# StmPulse-V1-InProgress.net
KiCad netlist of a schematic drawn in EAGLE
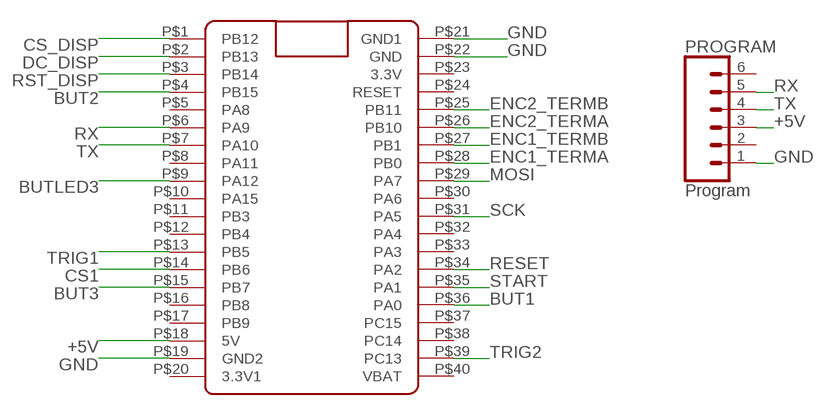
[diagram p0: schematic, sheet 1]
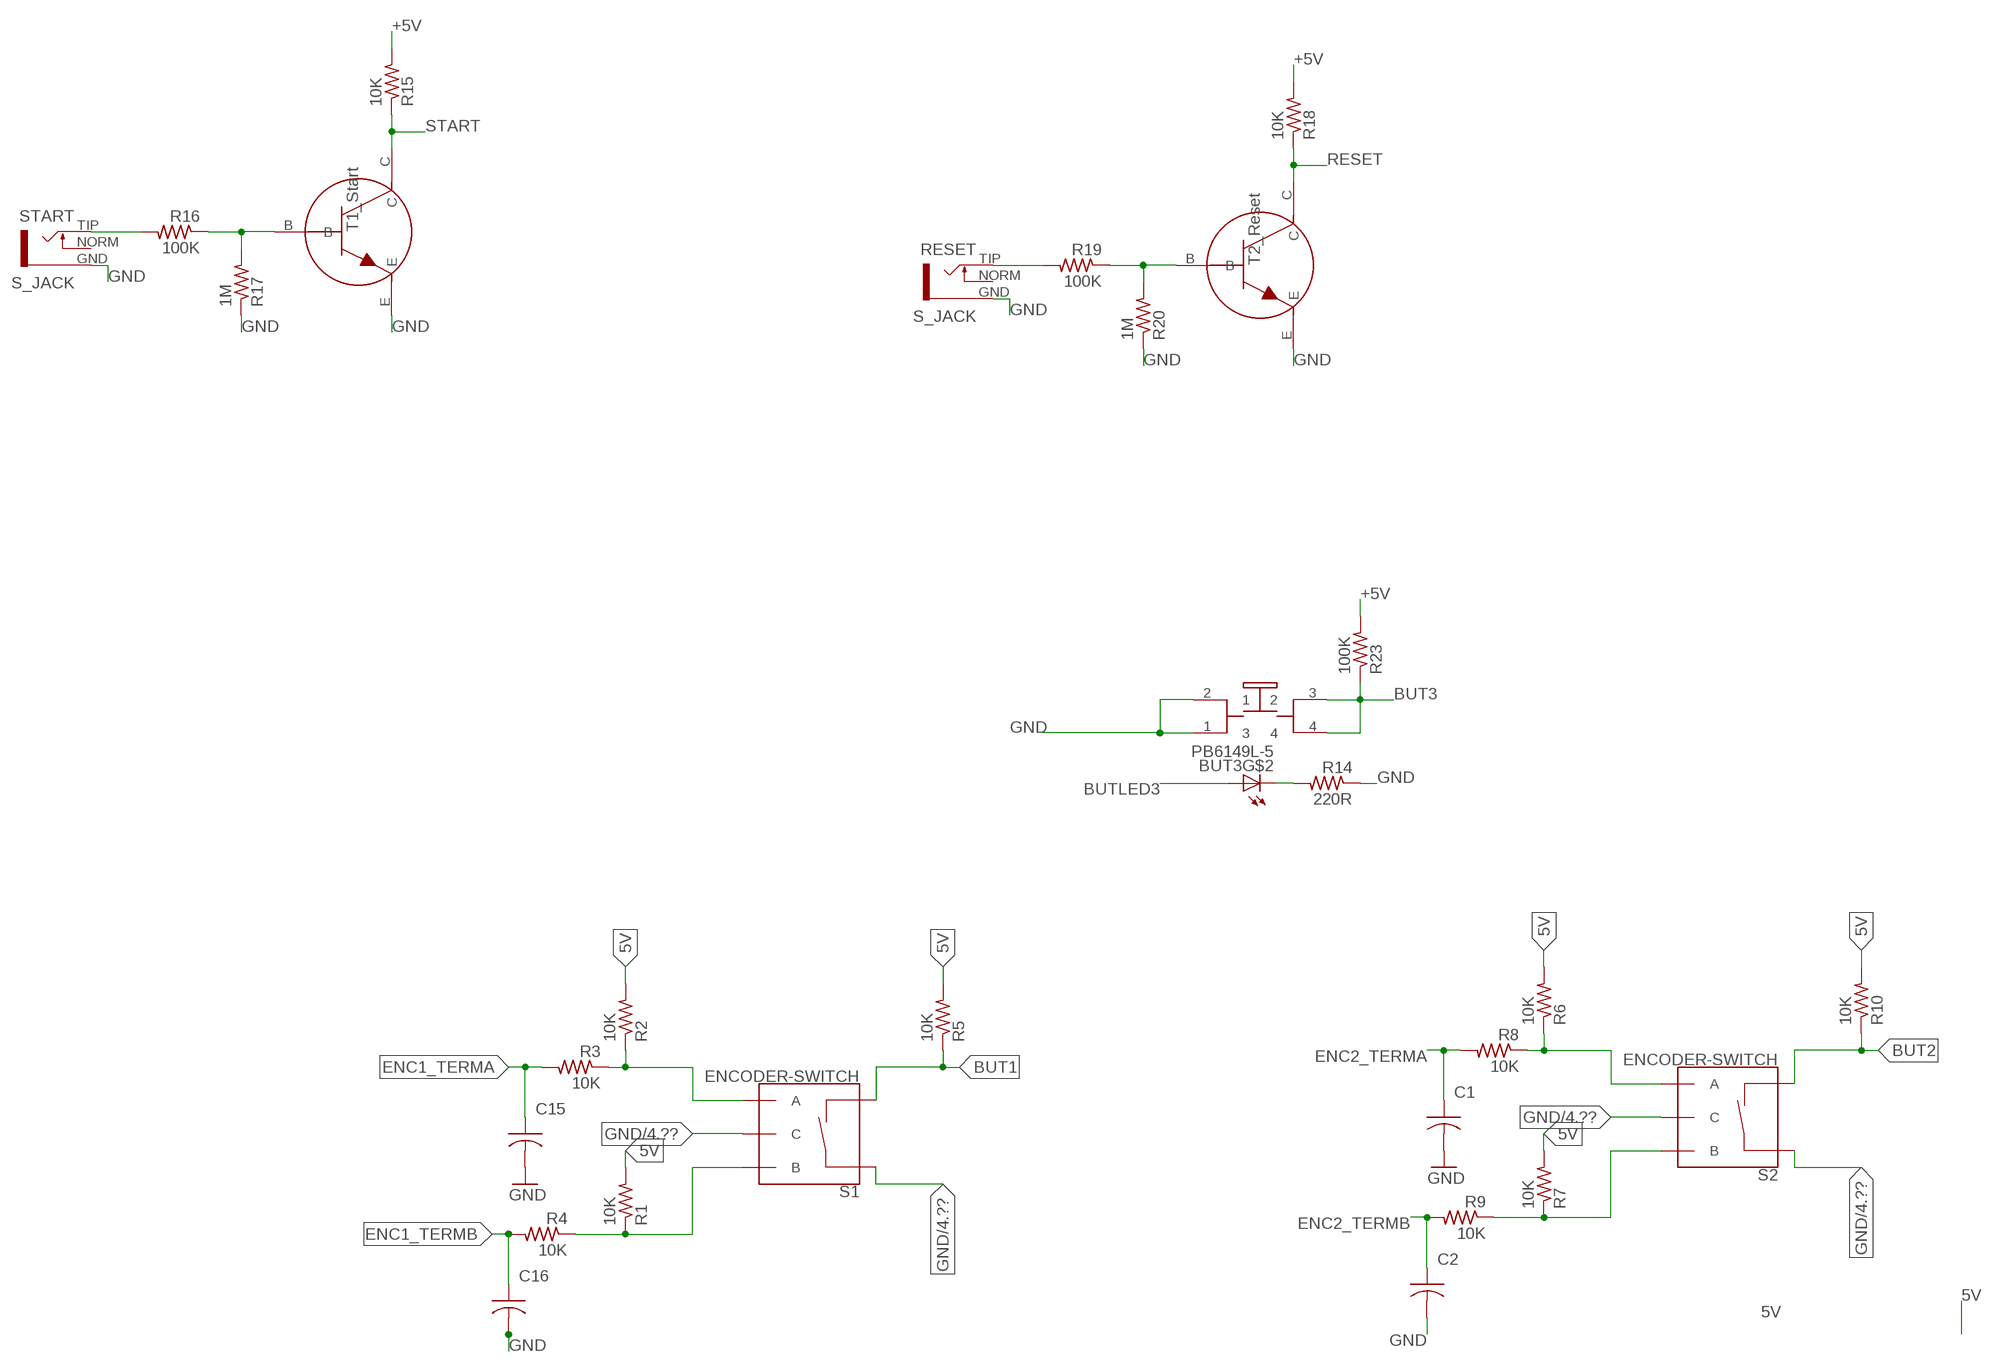
[diagram p1: schematic, sheet 2]
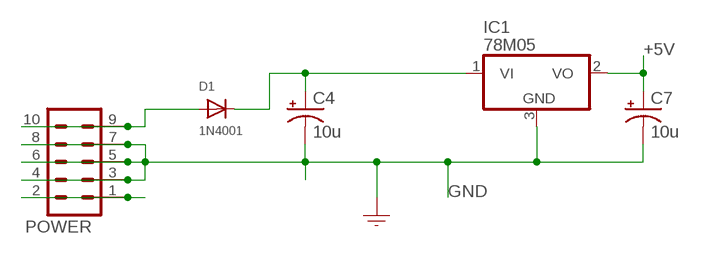
[diagram p2: schematic, sheet 3]
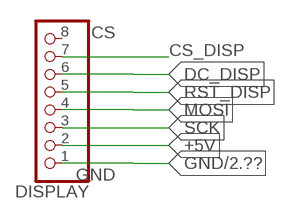
[diagram p3: schematic, sheet 4]
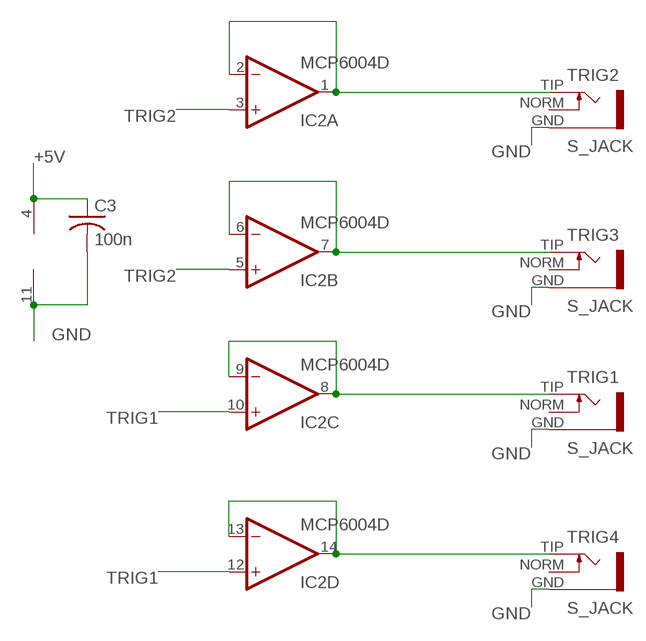
[diagram p4: schematic, sheet 5]
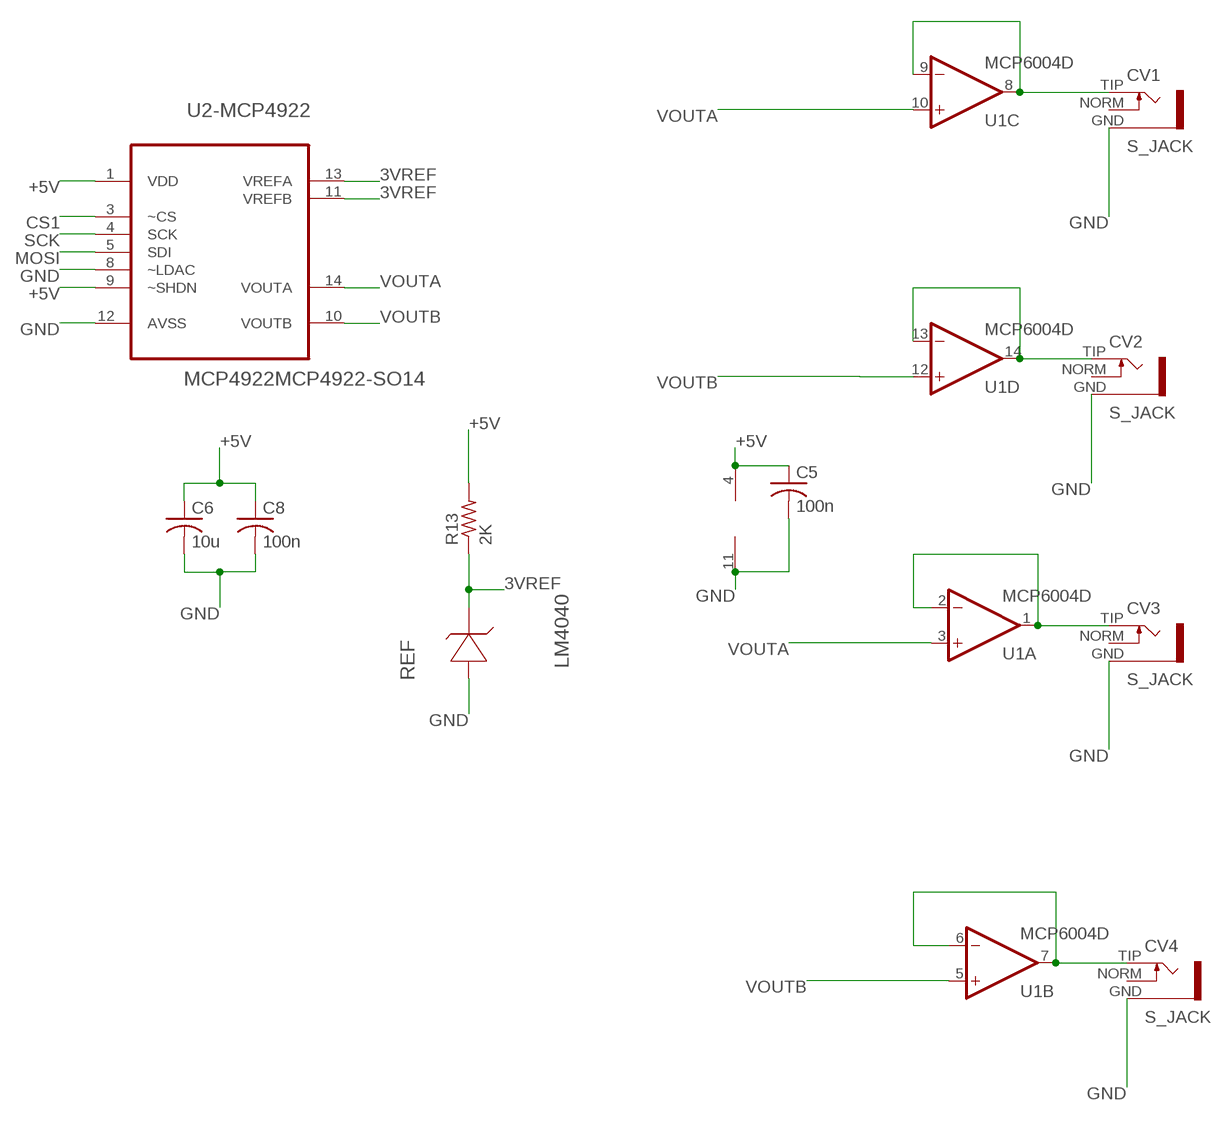
[diagram p5: schematic, sheet 6]

(export (version "E")
  (design (tool "Eeschema 10.0.6"))
  (components
    (comp (ref "PROGRAM")
      (value "Program")
      (footprint "eagle-import:1X06")
      (libsource (lib "eagle-import") (part "CONN_06SILK_FEMALE_PTH"))
    )
    (comp (ref "U$1")
      (value "Blue Pill")
      (footprint "eagle-import:BLUE_PILL")
      (libsource (lib "eagle-import") (part "BLUE_PILL"))
    )
    (comp (ref "DISPLAY")
      (value "MICROBUILDER_HEADER-1X8ROUND")
      (footprint "eagle-import:MICROBUILDER_1X08_ROUND")
      (libsource (lib "eagle-import") (part "MICROBUILDER_HEADER-1X8ROUND"))
    )
    (comp (ref "C3")
      (value "100n")
      (footprint "eagle-import:C0805K")
      (libsource (lib "eagle-import") (part "C-USC0805K"))
    )
    (comp (ref "IC2")
      (value "MCP6004D")
      (footprint "eagle-import:SO14")
      (libsource (lib "eagle-import") (part "MCP6004D"))
    )
    (comp (ref "TRIG1")
      (value "S_JACK")
      (footprint "eagle-import:S_JACK")
      (libsource (lib "eagle-import") (part "S_JACK"))
    )
    (comp (ref "TRIG2")
      (value "S_JACK")
      (footprint "eagle-import:S_JACK")
      (libsource (lib "eagle-import") (part "S_JACK"))
    )
    (comp (ref "TRIG3")
      (value "S_JACK")
      (footprint "eagle-import:S_JACK")
      (libsource (lib "eagle-import") (part "S_JACK"))
    )
    (comp (ref "TRIG4")
      (value "S_JACK")
      (footprint "eagle-import:S_JACK")
      (libsource (lib "eagle-import") (part "S_JACK"))
    )
    (comp (ref "C5")
      (value "100n")
      (footprint "eagle-import:C0805K")
      (libsource (lib "eagle-import") (part "C-USC0805K"))
    )
    (comp (ref "C6")
      (value "10u")
      (footprint "eagle-import:C0805K")
      (libsource (lib "eagle-import") (part "C-USC0805K"))
    )
    (comp (ref "C8")
      (value "100n")
      (footprint "eagle-import:C0805K")
      (libsource (lib "eagle-import") (part "C-USC0805K"))
    )
    (comp (ref "CV1")
      (value "S_JACK")
      (footprint "eagle-import:S_JACK")
      (libsource (lib "eagle-import") (part "S_JACK"))
    )
    (comp (ref "CV2")
      (value "S_JACK")
      (footprint "eagle-import:S_JACK")
      (libsource (lib "eagle-import") (part "S_JACK"))
    )
    (comp (ref "CV3")
      (value "S_JACK")
      (footprint "eagle-import:S_JACK")
      (libsource (lib "eagle-import") (part "S_JACK"))
    )
    (comp (ref "CV4")
      (value "S_JACK")
      (footprint "eagle-import:S_JACK")
      (libsource (lib "eagle-import") (part "S_JACK"))
    )
    (comp (ref "R13")
      (value "2K")
      (footprint "eagle-import:R0805")
      (libsource (lib "eagle-import") (part "R-US_R0805"))
    )
    (comp (ref "REF")
      (value "LM4040")
      (footprint "eagle-import:SOT95P237X112-3N")
      (fields
        (field (name "MPN") "LM4040A50IDBZT")
        (field (name "MPN_1") "LM4040A30IDBZT")
        (field (name "RS-PART") "809-6343")
      )
      (libsource (lib "eagle-import") (part "LM4040A30IDBZT"))
    )
    (comp (ref "U1")
      (value "MCP6004D")
      (footprint "eagle-import:SO14")
      (fields (field (name "RS-PART") "628-3481 (10)"))
      (libsource (lib "eagle-import") (part "MCP6004D"))
    )
    (comp (ref "U2-MCP4922")
      (value "MCP4922MCP4922-SO14")
      (footprint "eagle-import:SO14")
      (fields (field (name "RS-PART") "402-910 "))
      (libsource (lib "eagle-import") (part "MCP4922MCP4922-SO14"))
    )
    (comp (ref "C4")
      (value "10u")
      (footprint "eagle-import:153CLV-0505")
      (libsource (lib "eagle-import") (part "CAPACITOR_POL-US153CLV-0505"))
    )
    (comp (ref "C7")
      (value "10u")
      (footprint "eagle-import:153CLV-0505")
      (libsource (lib "eagle-import") (part "CAPACITOR_POL-US153CLV-0505"))
    )
    (comp (ref "D1")
      (value "1N4001")
      (footprint "eagle-import:SMADIODE")
      (libsource (lib "eagle-import") (part "DIODESMA"))
    )
    (comp (ref "IC1")
      (value "78M05")
      (footprint "eagle-import:TO252")
      (libsource (lib "eagle-import") (part "VOLTAGE_REG_POSDT05"))
    )
    (comp (ref "POWER")
      (value "CONN_05X2SHD_SMD")
      (footprint "eagle-import:2X5-SHROUDED_SMD")
      (libsource (lib "eagle-import") (part "CONN_05X2SHD_SMD"))
    )
    (comp (ref "BUT3")
      (value "PB6149L-5")
      (footprint "eagle-import:PB6149L")
      (libsource (lib "eagle-import") (part "PB6149L-5"))
    )
    (comp (ref "C1")
      (value "10nF")
      (footprint "eagle-import:C0805")
      (libsource (lib "eagle-import") (part "C-USC0805"))
    )
    (comp (ref "C2")
      (value "10nF")
      (footprint "eagle-import:C0805")
      (libsource (lib "eagle-import") (part "C-USC0805"))
    )
    (comp (ref "C15")
      (value "10nF")
      (footprint "eagle-import:C0805")
      (libsource (lib "eagle-import") (part "C-USC0805"))
    )
    (comp (ref "C16")
      (value "10nF")
      (footprint "eagle-import:C0805")
      (libsource (lib "eagle-import") (part "C-USC0805"))
    )
    (comp (ref "R1")
      (value "10K")
      (footprint "eagle-import:R0805")
      (libsource (lib "eagle-import") (part "R-US_R0805"))
    )
    (comp (ref "R2")
      (value "10K")
      (footprint "eagle-import:R0805")
      (libsource (lib "eagle-import") (part "R-US_R0805"))
    )
    (comp (ref "R3")
      (value "10K")
      (footprint "eagle-import:R0805")
      (libsource (lib "eagle-import") (part "R-US_R0805"))
    )
    (comp (ref "R4")
      (value "10K")
      (footprint "eagle-import:R0805")
      (libsource (lib "eagle-import") (part "R-US_R0805"))
    )
    (comp (ref "R5")
      (value "10K")
      (footprint "eagle-import:R0805")
      (libsource (lib "eagle-import") (part "R-US_R0805"))
    )
    (comp (ref "R6")
      (value "10K")
      (footprint "eagle-import:R0805")
      (libsource (lib "eagle-import") (part "R-US_R0805"))
    )
    (comp (ref "R7")
      (value "10K")
      (footprint "eagle-import:R0805")
      (libsource (lib "eagle-import") (part "R-US_R0805"))
    )
    (comp (ref "R8")
      (value "10K")
      (footprint "eagle-import:R0805")
      (libsource (lib "eagle-import") (part "R-US_R0805"))
    )
    (comp (ref "R9")
      (value "10K")
      (footprint "eagle-import:R0805")
      (libsource (lib "eagle-import") (part "R-US_R0805"))
    )
    (comp (ref "R10")
      (value "10K")
      (footprint "eagle-import:R0805")
      (libsource (lib "eagle-import") (part "R-US_R0805"))
    )
    (comp (ref "R14")
      (value "220R")
      (footprint "eagle-import:R0805")
      (libsource (lib "eagle-import") (part "R-US_R0805"))
    )
    (comp (ref "R15")
      (value "10K")
      (footprint "eagle-import:R0805")
      (libsource (lib "eagle-import") (part "R-US_R0805"))
    )
    (comp (ref "R16")
      (value "100K")
      (footprint "eagle-import:R0805")
      (libsource (lib "eagle-import") (part "R-US_R0805"))
    )
    (comp (ref "R17")
      (value "1M")
      (footprint "eagle-import:R0805")
      (libsource (lib "eagle-import") (part "R-US_R0805"))
    )
    (comp (ref "R18")
      (value "10K")
      (footprint "eagle-import:R0805")
      (libsource (lib "eagle-import") (part "R-US_R0805"))
    )
    (comp (ref "R19")
      (value "100K")
      (footprint "eagle-import:R0805")
      (libsource (lib "eagle-import") (part "R-US_R0805"))
    )
    (comp (ref "R20")
      (value "1M")
      (footprint "eagle-import:R0805")
      (libsource (lib "eagle-import") (part "R-US_R0805"))
    )
    (comp (ref "R23")
      (value "100K")
      (footprint "eagle-import:R0805")
      (libsource (lib "eagle-import") (part "R-US_R0805"))
    )
    (comp (ref "RESET")
      (value "S_JACK")
      (footprint "eagle-import:S_JACK")
      (libsource (lib "eagle-import") (part "S_JACK"))
    )
    (comp (ref "S1")
      (value "ENCODER-SWITCH")
      (footprint "eagle-import:ROTARY_ENC_PLAIN")
      (libsource (lib "eagle-import") (part "ENCODER-SWITCH"))
    )
    (comp (ref "S2")
      (value "ENCODER-SWITCH")
      (footprint "eagle-import:ROTARY_ENC_PLAIN")
      (libsource (lib "eagle-import") (part "ENCODER-SWITCH"))
    )
    (comp (ref "START")
      (value "S_JACK")
      (footprint "eagle-import:S_JACK")
      (libsource (lib "eagle-import") (part "S_JACK"))
    )
    (comp (ref "T1_CLOCK")
      (value "2N3904")
      (footprint "eagle-import:TRANSISTOR_SINGLE_N-TYPE")
      (fields (field (name "LABLEL") "T1_Start") (field (name "RS-PART") "725-8616 "))
      (libsource (lib "eagle-import") (part "TRANSISTOR_MMBT3904"))
    )
    (comp (ref "T2_RESET")
      (value "TRANSISTOR_MMBT3904")
      (footprint "eagle-import:TRANSISTOR_SINGLE_N-TYPE")
      (fields (field (name "LABEL") "T2_Reset") (field (name "RS-PART") "725-8616 "))
      (libsource (lib "eagle-import") (part "TRANSISTOR_MMBT3904"))
    )
  )
  (nets
    (net (code "1") (name "+5V") (class "Default")
      (node (ref "C3") (pin "1") (pinfunction "1_1") (pintype "passive"))
      (node (ref "C5") (pin "1") (pinfunction "1_1") (pintype "passive"))
      (node (ref "C6") (pin "1") (pinfunction "1_1") (pintype "passive"))
      (node (ref "C7") (pin "+") (pinfunction "+_+") (pintype "passive"))
      (node (ref "C8") (pin "1") (pinfunction "1_1") (pintype "passive"))
      (node (ref "DISPLAY") (pin "2") (pinfunction "2_2") (pintype "passive"))
      (node (ref "IC1") (pin "2") (pinfunction "VO_2") (pintype "passive"))
      (node (ref "IC2") (pin "4") (pinfunction "V+_4") (pintype "power_in"))
      (node (ref "PROGRAM") (pin "3") (pinfunction "3_3") (pintype "passive"))
      (node (ref "R13") (pin "2") (pinfunction "2_2") (pintype "passive"))
      (node (ref "R15") (pin "2") (pinfunction "2_2") (pintype "passive"))
      (node (ref "R18") (pin "2") (pinfunction "2_2") (pintype "passive"))
      (node (ref "R23") (pin "2") (pinfunction "2_2") (pintype "passive"))
      (node (ref "U$1") (pin "P$18") (pinfunction "5V_P$18") (pintype "bidirectional"))
      (node (ref "U1") (pin "4") (pinfunction "V+_4") (pintype "power_in"))
      (node (ref "U2-MCP4922") (pin "1") (pinfunction "VDD_1") (pintype "power_in"))
      (node (ref "U2-MCP4922") (pin "9") (pinfunction "~{SHDN}_9") (pintype "bidirectional"))
    )
    (net (code "2") (name "3VREF") (class "Default")
      (node (ref "R13") (pin "1") (pinfunction "1_1") (pintype "passive"))
      (node (ref "REF") (pin "1") (pinfunction "CATHODE_1") (pintype "output"))
      (node (ref "U2-MCP4922") (pin "11") (pinfunction "VREFB_11") (pintype "bidirectional"))
      (node (ref "U2-MCP4922") (pin "13") (pinfunction "VREFA_13") (pintype "input"))
    )
    (net (code "3") (name "5V") (class "Default")
      (node (ref "R1") (pin "2") (pinfunction "2_2") (pintype "passive"))
      (node (ref "R10") (pin "2") (pinfunction "2_2") (pintype "passive"))
      (node (ref "R2") (pin "2") (pinfunction "2_2") (pintype "passive"))
      (node (ref "R5") (pin "2") (pinfunction "2_2") (pintype "passive"))
      (node (ref "R6") (pin "2") (pinfunction "2_2") (pintype "passive"))
      (node (ref "R7") (pin "2") (pinfunction "2_2") (pintype "passive"))
    )
    (net (code "4") (name "BUT1") (class "Default")
      (node (ref "R5") (pin "1") (pinfunction "1_1") (pintype "passive"))
      (node (ref "S1") (pin "SW-") (pinfunction "SW-_SW-") (pintype "bidirectional"))
      (node (ref "U$1") (pin "P$36") (pinfunction "PA0_P$36") (pintype "bidirectional"))
    )
    (net (code "5") (name "BUT2") (class "Default")
      (node (ref "R10") (pin "1") (pinfunction "1_1") (pintype "passive"))
      (node (ref "S2") (pin "SW-") (pinfunction "SW-_SW-") (pintype "bidirectional"))
      (node (ref "U$1") (pin "P$4") (pinfunction "PB15_P$4") (pintype "bidirectional"))
    )
    (net (code "6") (name "BUT3") (class "Default")
      (node (ref "BUT3") (pin "3") (pinfunction "2_3") (pintype "bidirectional"))
      (node (ref "BUT3") (pin "4") (pinfunction "4_4") (pintype "bidirectional"))
      (node (ref "R23") (pin "1") (pinfunction "1_1") (pintype "passive"))
      (node (ref "U$1") (pin "P$15") (pinfunction "PB7_P$15") (pintype "bidirectional"))
    )
    (net (code "7") (name "BUTLED3") (class "Default")
      (node (ref "BUT3") (pin "A") (pinfunction "A_A") (pintype "passive"))
      (node (ref "U$1") (pin "P$9") (pinfunction "PA12_P$9") (pintype "bidirectional"))
    )
    (net (code "8") (name "CS1") (class "Default")
      (node (ref "U$1") (pin "P$14") (pinfunction "PB6_P$14") (pintype "bidirectional"))
      (node (ref "U2-MCP4922") (pin "3") (pinfunction "~{CS}_3") (pintype "input"))
    )
    (net (code "9") (name "CS_DISP") (class "Default")
      (node (ref "DISPLAY") (pin "7") (pinfunction "7_7") (pintype "passive"))
      (node (ref "U$1") (pin "P$1") (pinfunction "PB12_P$1") (pintype "bidirectional"))
    )
    (net (code "10") (name "DC_DISP") (class "Default")
      (node (ref "DISPLAY") (pin "6") (pinfunction "6_6") (pintype "passive"))
      (node (ref "U$1") (pin "P$2") (pinfunction "PB13_P$2") (pintype "bidirectional"))
    )
    (net (code "11") (name "ENC1_TERMA") (class "Default")
      (node (ref "C15") (pin "1") (pinfunction "1_1") (pintype "passive"))
      (node (ref "R3") (pin "2") (pinfunction "2_2") (pintype "passive"))
      (node (ref "U$1") (pin "P$28") (pinfunction "PB0_P$28") (pintype "bidirectional"))
    )
    (net (code "12") (name "ENC1_TERMB") (class "Default")
      (node (ref "C16") (pin "1") (pinfunction "1_1") (pintype "passive"))
      (node (ref "R4") (pin "2") (pinfunction "2_2") (pintype "passive"))
      (node (ref "U$1") (pin "P$27") (pinfunction "PB1_P$27") (pintype "bidirectional"))
    )
    (net (code "13") (name "ENC2_TERMA") (class "Default")
      (node (ref "C1") (pin "1") (pinfunction "1_1") (pintype "passive"))
      (node (ref "R8") (pin "2") (pinfunction "2_2") (pintype "passive"))
      (node (ref "U$1") (pin "P$26") (pinfunction "PB10_P$26") (pintype "bidirectional"))
    )
    (net (code "14") (name "ENC2_TERMB") (class "Default")
      (node (ref "C2") (pin "1") (pinfunction "1_1") (pintype "passive"))
      (node (ref "R9") (pin "2") (pinfunction "2_2") (pintype "passive"))
      (node (ref "U$1") (pin "P$25") (pinfunction "PB11_P$25") (pintype "bidirectional"))
    )
    (net (code "15") (name "GND") (class "Default")
      (node (ref "BUT3") (pin "1") (pinfunction "3_1") (pintype "bidirectional"))
      (node (ref "BUT3") (pin "2") (pinfunction "1_2") (pintype "bidirectional"))
      (node (ref "C1") (pin "2") (pinfunction "2_2") (pintype "passive"))
      (node (ref "C15") (pin "2") (pinfunction "2_2") (pintype "passive"))
      (node (ref "C16") (pin "2") (pinfunction "2_2") (pintype "passive"))
      (node (ref "C2") (pin "2") (pinfunction "2_2") (pintype "passive"))
      (node (ref "C3") (pin "2") (pinfunction "2_2") (pintype "passive"))
      (node (ref "C4") (pin "-") (pinfunction "-_-") (pintype "passive"))
      (node (ref "C5") (pin "2") (pinfunction "2_2") (pintype "passive"))
      (node (ref "C6") (pin "2") (pinfunction "2_2") (pintype "passive"))
      (node (ref "C7") (pin "-") (pinfunction "-_-") (pintype "passive"))
      (node (ref "C8") (pin "2") (pinfunction "2_2") (pintype "passive"))
      (node (ref "CV1") (pin "GND") (pinfunction "GND_GND") (pintype "passive"))
      (node (ref "CV2") (pin "GND") (pinfunction "GND_GND") (pintype "passive"))
      (node (ref "CV3") (pin "GND") (pinfunction "GND_GND") (pintype "passive"))
      (node (ref "CV4") (pin "GND") (pinfunction "GND_GND") (pintype "passive"))
      (node (ref "DISPLAY") (pin "1") (pinfunction "1_1") (pintype "passive"))
      (node (ref "IC1") (pin "3") (pinfunction "GND_3") (pintype "passive"))
      (node (ref "IC2") (pin "11") (pinfunction "V-_11") (pintype "power_in"))
      (node (ref "POWER") (pin "3") (pinfunction "3_3") (pintype "passive"))
      (node (ref "POWER") (pin "4") (pinfunction "4_4") (pintype "passive"))
      (node (ref "POWER") (pin "5") (pinfunction "5_5") (pintype "passive"))
      (node (ref "POWER") (pin "6") (pinfunction "6_6") (pintype "passive"))
      (node (ref "POWER") (pin "7") (pinfunction "7_7") (pintype "passive"))
      (node (ref "POWER") (pin "8") (pinfunction "8_8") (pintype "passive"))
      (node (ref "PROGRAM") (pin "1") (pinfunction "1_1") (pintype "passive"))
      (node (ref "R14") (pin "1") (pinfunction "1_1") (pintype "passive"))
      (node (ref "R17") (pin "1") (pinfunction "1_1") (pintype "passive"))
      (node (ref "R20") (pin "1") (pinfunction "1_1") (pintype "passive"))
      (node (ref "REF") (pin "2") (pinfunction "ANODE_2") (pintype "input"))
      (node (ref "RESET") (pin "GND") (pinfunction "GND_GND") (pintype "passive"))
      (node (ref "S1") (pin "C") (pinfunction "C_C") (pintype "bidirectional"))
      (node (ref "S1") (pin "SW+") (pinfunction "SW+_SW+") (pintype "bidirectional"))
      (node (ref "S2") (pin "C") (pinfunction "C_C") (pintype "bidirectional"))
      (node (ref "S2") (pin "SW+") (pinfunction "SW+_SW+") (pintype "bidirectional"))
      (node (ref "START") (pin "GND") (pinfunction "GND_GND") (pintype "passive"))
      (node (ref "T1_CLOCK") (pin "E") (pinfunction "E_E") (pintype "bidirectional"))
      (node (ref "T2_RESET") (pin "E") (pinfunction "E_E") (pintype "bidirectional"))
      (node (ref "TRIG1") (pin "GND") (pinfunction "GND_GND") (pintype "passive"))
      (node (ref "TRIG2") (pin "GND") (pinfunction "GND_GND") (pintype "passive"))
      (node (ref "TRIG3") (pin "GND") (pinfunction "GND_GND") (pintype "passive"))
      (node (ref "TRIG4") (pin "GND") (pinfunction "GND_GND") (pintype "passive"))
      (node (ref "U$1") (pin "P$19") (pinfunction "GND2_P$19") (pintype "bidirectional"))
      (node (ref "U$1") (pin "P$21") (pinfunction "GND1_P$21") (pintype "power_in"))
      (node (ref "U$1") (pin "P$22") (pinfunction "GND_P$22") (pintype "bidirectional"))
      (node (ref "U1") (pin "11") (pinfunction "V-_11") (pintype "power_in"))
      (node (ref "U2-MCP4922") (pin "12") (pinfunction "AVSS_12") (pintype "passive"))
      (node (ref "U2-MCP4922") (pin "8") (pinfunction "~{LDAC}_8") (pintype "input"))
    )
    (net (code "16") (name "MOSI") (class "Default")
      (node (ref "DISPLAY") (pin "4") (pinfunction "4_4") (pintype "passive"))
      (node (ref "U$1") (pin "P$29") (pinfunction "PA7_P$29") (pintype "bidirectional"))
      (node (ref "U2-MCP4922") (pin "5") (pinfunction "SDI_5") (pintype "input"))
    )
    (net (code "17") (name "Net-(BUT3B-C)") (class "Default")
      (node (ref "BUT3") (pin "K") (pinfunction "C_K") (pintype "passive"))
      (node (ref "R14") (pin "2") (pinfunction "2_2") (pintype "passive"))
    )
    (net (code "18") (name "Net-(D1-PadA)") (class "Default")
      (node (ref "D1") (pin "A") (pinfunction "A_A") (pintype "passive"))
      (node (ref "POWER") (pin "10") (pinfunction "10_10") (pintype "passive"))
      (node (ref "POWER") (pin "9") (pinfunction "9_9") (pintype "passive"))
    )
    (net (code "19") (name "Net-(IC1-VI)") (class "Default")
      (node (ref "C4") (pin "+") (pinfunction "+_+") (pintype "passive"))
      (node (ref "D1") (pin "C") (pinfunction "C_C") (pintype "passive"))
      (node (ref "IC1") (pin "1") (pinfunction "VI_1") (pintype "input"))
    )
    (net (code "20") (name "Net-(IC2A--IN)") (class "Default")
      (node (ref "IC2") (pin "1") (pinfunction "OUT_1") (pintype "output"))
      (node (ref "IC2") (pin "2") (pinfunction "-IN_2") (pintype "input"))
      (node (ref "TRIG2") (pin "TIP") (pinfunction "TIP_TIP") (pintype "passive"))
    )
    (net (code "21") (name "Net-(IC2B--IN)") (class "Default")
      (node (ref "IC2") (pin "6") (pinfunction "-IN_6") (pintype "input"))
      (node (ref "IC2") (pin "7") (pinfunction "OUT_7") (pintype "output"))
      (node (ref "TRIG3") (pin "TIP") (pinfunction "TIP_TIP") (pintype "passive"))
    )
    (net (code "22") (name "Net-(IC2C--IN)") (class "Default")
      (node (ref "IC2") (pin "8") (pinfunction "OUT_8") (pintype "output"))
      (node (ref "IC2") (pin "9") (pinfunction "-IN_9") (pintype "input"))
      (node (ref "TRIG1") (pin "TIP") (pinfunction "TIP_TIP") (pintype "passive"))
    )
    (net (code "23") (name "Net-(IC2D--IN)") (class "Default")
      (node (ref "IC2") (pin "13") (pinfunction "-IN_13") (pintype "input"))
      (node (ref "IC2") (pin "14") (pinfunction "OUT_14") (pintype "output"))
      (node (ref "TRIG4") (pin "TIP") (pinfunction "TIP_TIP") (pintype "passive"))
    )
    (net (code "24") (name "Net-(POWER-Pad1)") (class "Default")
      (node (ref "POWER") (pin "1") (pinfunction "1_1") (pintype "passive"))
      (node (ref "POWER") (pin "2") (pinfunction "2_2") (pintype "passive"))
    )
    (net (code "25") (name "Net-(R1-Pad1)") (class "Default")
      (node (ref "R1") (pin "1") (pinfunction "1_1") (pintype "passive"))
      (node (ref "R4") (pin "1") (pinfunction "1_1") (pintype "passive"))
      (node (ref "S1") (pin "B") (pinfunction "B_B") (pintype "bidirectional"))
    )
    (net (code "26") (name "Net-(R2-Pad1)") (class "Default")
      (node (ref "R2") (pin "1") (pinfunction "1_1") (pintype "passive"))
      (node (ref "R3") (pin "1") (pinfunction "1_1") (pintype "passive"))
      (node (ref "S1") (pin "A") (pinfunction "A_A") (pintype "bidirectional"))
    )
    (net (code "27") (name "Net-(R6-Pad1)") (class "Default")
      (node (ref "R6") (pin "1") (pinfunction "1_1") (pintype "passive"))
      (node (ref "R8") (pin "1") (pinfunction "1_1") (pintype "passive"))
      (node (ref "S2") (pin "A") (pinfunction "A_A") (pintype "bidirectional"))
    )
    (net (code "28") (name "Net-(R7-Pad1)") (class "Default")
      (node (ref "R7") (pin "1") (pinfunction "1_1") (pintype "passive"))
      (node (ref "R9") (pin "1") (pinfunction "1_1") (pintype "passive"))
      (node (ref "S2") (pin "B") (pinfunction "B_B") (pintype "bidirectional"))
    )
    (net (code "29") (name "Net-(R16-Pad1)") (class "Default")
      (node (ref "R16") (pin "1") (pinfunction "1_1") (pintype "passive"))
      (node (ref "R17") (pin "2") (pinfunction "2_2") (pintype "passive"))
      (node (ref "T1_CLOCK") (pin "B") (pinfunction "B_B") (pintype "bidirectional"))
    )
    (net (code "30") (name "Net-(R16-Pad2)") (class "Default")
      (node (ref "R16") (pin "2") (pinfunction "2_2") (pintype "passive"))
      (node (ref "START") (pin "TIP") (pinfunction "TIP_TIP") (pintype "passive"))
    )
    (net (code "31") (name "Net-(R19-Pad1)") (class "Default")
      (node (ref "R19") (pin "1") (pinfunction "1_1") (pintype "passive"))
      (node (ref "R20") (pin "2") (pinfunction "2_2") (pintype "passive"))
      (node (ref "T2_RESET") (pin "B") (pinfunction "B_B") (pintype "bidirectional"))
    )
    (net (code "32") (name "Net-(R19-Pad2)") (class "Default")
      (node (ref "R19") (pin "2") (pinfunction "2_2") (pintype "passive"))
      (node (ref "RESET") (pin "TIP") (pinfunction "TIP_TIP") (pintype "passive"))
    )
    (net (code "33") (name "Net-(U1A--IN)") (class "Default")
      (node (ref "CV3") (pin "TIP") (pinfunction "TIP_TIP") (pintype "passive"))
      (node (ref "U1") (pin "1") (pinfunction "OUT_1") (pintype "output"))
      (node (ref "U1") (pin "2") (pinfunction "-IN_2") (pintype "input"))
    )
    (net (code "34") (name "Net-(U1B--IN)") (class "Default")
      (node (ref "CV4") (pin "TIP") (pinfunction "TIP_TIP") (pintype "passive"))
      (node (ref "U1") (pin "6") (pinfunction "-IN_6") (pintype "input"))
      (node (ref "U1") (pin "7") (pinfunction "OUT_7") (pintype "output"))
    )
    (net (code "35") (name "Net-(U1C--IN)") (class "Default")
      (node (ref "CV1") (pin "TIP") (pinfunction "TIP_TIP") (pintype "passive"))
      (node (ref "U1") (pin "8") (pinfunction "OUT_8") (pintype "output"))
      (node (ref "U1") (pin "9") (pinfunction "-IN_9") (pintype "input"))
    )
    (net (code "36") (name "Net-(U1D--IN)") (class "Default")
      (node (ref "CV2") (pin "TIP") (pinfunction "TIP_TIP") (pintype "passive"))
      (node (ref "U1") (pin "13") (pinfunction "-IN_13") (pintype "input"))
      (node (ref "U1") (pin "14") (pinfunction "OUT_14") (pintype "output"))
    )
    (net (code "37") (name "RESET") (class "Default")
      (node (ref "R18") (pin "1") (pinfunction "1_1") (pintype "passive"))
      (node (ref "T2_RESET") (pin "C") (pinfunction "C_C") (pintype "bidirectional"))
      (node (ref "U$1") (pin "P$34") (pinfunction "PA2_P$34") (pintype "bidirectional"))
    )
    (net (code "38") (name "RST_DISP") (class "Default")
      (node (ref "DISPLAY") (pin "5") (pinfunction "5_5") (pintype "passive"))
      (node (ref "U$1") (pin "P$3") (pinfunction "PB14_P$3") (pintype "bidirectional"))
    )
    (net (code "39") (name "RX") (class "Default")
      (node (ref "PROGRAM") (pin "5") (pinfunction "5_5") (pintype "passive"))
      (node (ref "U$1") (pin "P$6") (pinfunction "PA9_P$6") (pintype "bidirectional"))
    )
    (net (code "40") (name "SCK") (class "Default")
      (node (ref "DISPLAY") (pin "3") (pinfunction "3_3") (pintype "passive"))
      (node (ref "U$1") (pin "P$31") (pinfunction "PA5_P$31") (pintype "bidirectional"))
      (node (ref "U2-MCP4922") (pin "4") (pinfunction "SCK_4") (pintype "input"))
    )
    (net (code "41") (name "START") (class "Default")
      (node (ref "R15") (pin "1") (pinfunction "1_1") (pintype "passive"))
      (node (ref "T1_CLOCK") (pin "C") (pinfunction "C_C") (pintype "bidirectional"))
      (node (ref "U$1") (pin "P$35") (pinfunction "PA1_P$35") (pintype "bidirectional"))
    )
    (net (code "42") (name "TRIG1") (class "Default")
      (node (ref "IC2") (pin "10") (pinfunction "+IN_10") (pintype "input"))
      (node (ref "IC2") (pin "12") (pinfunction "+IN_12") (pintype "input"))
      (node (ref "U$1") (pin "P$13") (pinfunction "PB5_P$13") (pintype "bidirectional"))
    )
    (net (code "43") (name "TRIG2") (class "Default")
      (node (ref "IC2") (pin "3") (pinfunction "+IN_3") (pintype "input"))
      (node (ref "IC2") (pin "5") (pinfunction "+IN_5") (pintype "input"))
      (node (ref "U$1") (pin "P$39") (pinfunction "PC13_P$39") (pintype "bidirectional"))
    )
    (net (code "44") (name "TX") (class "Default")
      (node (ref "PROGRAM") (pin "4") (pinfunction "4_4") (pintype "passive"))
      (node (ref "U$1") (pin "P$7") (pinfunction "PA10_P$7") (pintype "bidirectional"))
    )
    (net (code "45") (name "VOUTA") (class "Default")
      (node (ref "U1") (pin "10") (pinfunction "+IN_10") (pintype "input"))
      (node (ref "U1") (pin "3") (pinfunction "+IN_3") (pintype "input"))
      (node (ref "U2-MCP4922") (pin "14") (pinfunction "VOUTA_14") (pintype "output"))
    )
    (net (code "46") (name "VOUTB") (class "Default")
      (node (ref "U1") (pin "12") (pinfunction "+IN_12") (pintype "input"))
      (node (ref "U1") (pin "5") (pinfunction "+IN_5") (pintype "input"))
      (node (ref "U2-MCP4922") (pin "10") (pinfunction "VOUTB_10") (pintype "output"))
    )
    (net (code "47") (name "unconnected-(CV1-PadNORM)") (class "Default")
      (node (ref "CV1") (pin "NORM") (pinfunction "NORM_NORM") (pintype "passive"))
    )
    (net (code "48") (name "unconnected-(CV2-PadNORM)") (class "Default")
      (node (ref "CV2") (pin "NORM") (pinfunction "NORM_NORM") (pintype "passive"))
    )
    (net (code "49") (name "unconnected-(CV3-PadNORM)") (class "Default")
      (node (ref "CV3") (pin "NORM") (pinfunction "NORM_NORM") (pintype "passive"))
    )
    (net (code "50") (name "unconnected-(CV4-PadNORM)") (class "Default")
      (node (ref "CV4") (pin "NORM") (pinfunction "NORM_NORM") (pintype "passive"))
    )
    (net (code "51") (name "unconnected-(DISPLAY-Pad8)") (class "Default")
      (node (ref "DISPLAY") (pin "8") (pinfunction "8_8") (pintype "passive"))
    )
    (net (code "52") (name "unconnected-(PROGRAM-Pad2)") (class "Default")
      (node (ref "PROGRAM") (pin "2") (pinfunction "2_2") (pintype "passive"))
    )
    (net (code "53") (name "unconnected-(PROGRAM-Pad6)") (class "Default")
      (node (ref "PROGRAM") (pin "6") (pinfunction "6_6") (pintype "passive"))
    )
    (net (code "54") (name "unconnected-(REF-NC-Pad3)") (class "Default")
      (node (ref "REF") (pin "3") (pinfunction "NC_3") (pintype "no_connect"))
    )
    (net (code "55") (name "unconnected-(RESET-PadNORM)") (class "Default")
      (node (ref "RESET") (pin "NORM") (pinfunction "NORM_NORM") (pintype "passive"))
    )
    (net (code "56") (name "unconnected-(START-PadNORM)") (class "Default")
      (node (ref "START") (pin "NORM") (pinfunction "NORM_NORM") (pintype "passive"))
    )
    (net (code "57") (name "unconnected-(TRIG1-PadNORM)") (class "Default")
      (node (ref "TRIG1") (pin "NORM") (pinfunction "NORM_NORM") (pintype "passive"))
    )
    (net (code "58") (name "unconnected-(TRIG2-PadNORM)") (class "Default")
      (node (ref "TRIG2") (pin "NORM") (pinfunction "NORM_NORM") (pintype "passive"))
    )
    (net (code "59") (name "unconnected-(TRIG3-PadNORM)") (class "Default")
      (node (ref "TRIG3") (pin "NORM") (pinfunction "NORM_NORM") (pintype "passive"))
    )
    (net (code "60") (name "unconnected-(TRIG4-PadNORM)") (class "Default")
      (node (ref "TRIG4") (pin "NORM") (pinfunction "NORM_NORM") (pintype "passive"))
    )
    (net (code "61") (name "unconnected-(U$1-3.3V-PadP$23)") (class "Default")
      (node (ref "U$1") (pin "P$23") (pinfunction "3.3V_P$23") (pintype "bidirectional"))
    )
    (net (code "62") (name "unconnected-(U$1-3.3V1-PadP$20)") (class "Default")
      (node (ref "U$1") (pin "P$20") (pinfunction "3.3V1_P$20") (pintype "bidirectional"))
    )
    (net (code "63") (name "unconnected-(U$1-PA3-PadP$33)") (class "Default")
      (node (ref "U$1") (pin "P$33") (pinfunction "PA3_P$33") (pintype "bidirectional"))
    )
    (net (code "64") (name "unconnected-(U$1-PA4-PadP$32)") (class "Default")
      (node (ref "U$1") (pin "P$32") (pinfunction "PA4_P$32") (pintype "bidirectional"))
    )
    (net (code "65") (name "unconnected-(U$1-PA6-PadP$30)") (class "Default")
      (node (ref "U$1") (pin "P$30") (pinfunction "PA6_P$30") (pintype "bidirectional"))
    )
    (net (code "66") (name "unconnected-(U$1-PA8-PadP$5)") (class "Default")
      (node (ref "U$1") (pin "P$5") (pinfunction "PA8_P$5") (pintype "bidirectional"))
    )
    (net (code "67") (name "unconnected-(U$1-PA11-PadP$8)") (class "Default")
      (node (ref "U$1") (pin "P$8") (pinfunction "PA11_P$8") (pintype "bidirectional"))
    )
    (net (code "68") (name "unconnected-(U$1-PA15-PadP$10)") (class "Default")
      (node (ref "U$1") (pin "P$10") (pinfunction "PA15_P$10") (pintype "bidirectional"))
    )
    (net (code "69") (name "unconnected-(U$1-PB3-PadP$11)") (class "Default")
      (node (ref "U$1") (pin "P$11") (pinfunction "PB3_P$11") (pintype "bidirectional"))
    )
    (net (code "70") (name "unconnected-(U$1-PB4-PadP$12)") (class "Default")
      (node (ref "U$1") (pin "P$12") (pinfunction "PB4_P$12") (pintype "bidirectional"))
    )
    (net (code "71") (name "unconnected-(U$1-PB8-PadP$16)") (class "Default")
      (node (ref "U$1") (pin "P$16") (pinfunction "PB8_P$16") (pintype "bidirectional"))
    )
    (net (code "72") (name "unconnected-(U$1-PB9-PadP$17)") (class "Default")
      (node (ref "U$1") (pin "P$17") (pinfunction "PB9_P$17") (pintype "bidirectional"))
    )
    (net (code "73") (name "unconnected-(U$1-PC14-PadP$38)") (class "Default")
      (node (ref "U$1") (pin "P$38") (pinfunction "PC14_P$38") (pintype "bidirectional"))
    )
    (net (code "74") (name "unconnected-(U$1-PC15-PadP$37)") (class "Default")
      (node (ref "U$1") (pin "P$37") (pinfunction "PC15_P$37") (pintype "bidirectional"))
    )
    (net (code "75") (name "unconnected-(U$1-RESET-PadP$24)") (class "Default")
      (node (ref "U$1") (pin "P$24") (pinfunction "RESET_P$24") (pintype "bidirectional"))
    )
    (net (code "76") (name "unconnected-(U$1-VBAT-PadP$40)") (class "Default")
      (node (ref "U$1") (pin "P$40") (pinfunction "VBAT_P$40") (pintype "bidirectional"))
    )
  )
)
